# CAN_PHY.net
KiCad netlist of a schematic drawn in Altium Designer
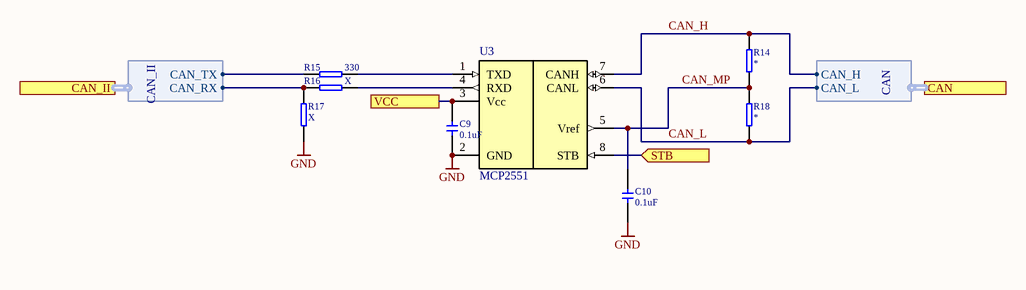
[diagram p0: CAN_PHY.SchDoc]

(export (version "E")
  (design (tool "Eeschema 10.0.6"))
  (components
    (comp (ref "C9")
      (value "0.1uF")
      (footprint "CERCAP 0603")
      (description "Capacitor")
      (fields (field (name "Comment") "CERCAP 0603 0.1uF * X7R"))
      (libsource (lib "!main") (part "!Capacitor"))
    )
    (comp (ref "C10")
      (value "0.1uF")
      (footprint "CERCAP 0603")
      (description "Capacitor")
      (fields (field (name "Comment") "CERCAP 0603 0.1uF * X7R"))
      (libsource (lib "!main") (part "!Capacitor"))
    )
    (comp (ref "R14")
      (value "RES 0603 *")
      (footprint "RES 0603")
      (description "Resistor")
      (fields (field (name "ALTIUM_VALUE") "*"))
      (libsource (lib "!main") (part "!Resistor"))
    )
    (comp (ref "R15")
      (value "330")
      (footprint "RES 0603")
      (description "Resistor")
      (fields (field (name "Comment") "RES 0603 330"))
      (libsource (lib "!main") (part "!Resistor"))
    )
    (comp (ref "R16")
      (value "X")
      (footprint "RES 0603")
      (description "Resistor")
      (fields (field (name "Comment") "RES 0603 X"))
      (libsource (lib "!main") (part "!Resistor"))
    )
    (comp (ref "R17")
      (value "X")
      (footprint "RES 0603")
      (description "Resistor")
      (fields (field (name "Comment") "RES 0603 X"))
      (libsource (lib "!main") (part "!Resistor"))
    )
    (comp (ref "R18")
      (value "RES 0603 *")
      (footprint "RES 0603")
      (description "Resistor")
      (fields (field (name "ALTIUM_VALUE") "*"))
      (libsource (lib "!main") (part "!Resistor"))
    )
    (comp (ref "U3")
      (value "MCP2551")
      (footprint "SO-8")
      (description "CAN PHY")
      (libsource (lib "interfaces") (part "CAN_PHY"))
    )
  )
  (nets
    (net (code "3") (name "/CAN_H") (class "Default")
      (node (ref "R14") (pin "2") (pinfunction "12_2") (pintype "passive"))
      (node (ref "U3") (pin "7") (pinfunction "CANH_7") (pintype "bidirectional"))
    )
    (net (code "4") (name "/CAN_L") (class "Default")
      (node (ref "R18") (pin "1") (pinfunction "11_1") (pintype "passive"))
      (node (ref "U3") (pin "6") (pinfunction "CANL_6") (pintype "bidirectional"))
    )
    (net (code "5") (name "/CAN_MP") (class "Default")
      (node (ref "C10") (pin "2") (pintype "passive"))
      (node (ref "R14") (pin "1") (pinfunction "11_1") (pintype "passive"))
      (node (ref "R18") (pin "2") (pinfunction "12_2") (pintype "passive"))
      (node (ref "U3") (pin "5") (pinfunction "Vref_5") (pintype "output"))
    )
    (net (code "6") (name "/CAN_RX") (class "Default")
      (node (ref "R16") (pin "1") (pinfunction "11_1") (pintype "passive"))
      (node (ref "R17") (pin "2") (pinfunction "12_2") (pintype "passive"))
    )
    (net (code "7") (name "/CAN_TX") (class "Default")
      (node (ref "R15") (pin "1") (pinfunction "11_1") (pintype "passive"))
    )
    (net (code "8") (name "/STB") (class "Default")
      (node (ref "U3") (pin "8") (pinfunction "STB_8") (pintype "input"))
    )
    (net (code "9") (name "/VCC") (class "Default")
      (node (ref "C9") (pin "2") (pintype "passive"))
      (node (ref "U3") (pin "3") (pinfunction "Vcc_3") (pintype "power_in"))
    )
    (net (code "12") (name "GND") (class "Default")
      (node (ref "C10") (pin "1") (pintype "passive"))
      (node (ref "C9") (pin "1") (pintype "passive"))
      (node (ref "R17") (pin "1") (pinfunction "11_1") (pintype "passive"))
      (node (ref "U3") (pin "2") (pinfunction "GND_2") (pintype "power_in"))
    )
    (net (code "13") (name "Net-(R15-12)") (class "Default")
      (node (ref "R15") (pin "2") (pinfunction "12_2") (pintype "passive"))
      (node (ref "U3") (pin "1") (pinfunction "TXD_1") (pintype "input"))
    )
    (net (code "14") (name "Net-(R16-12)") (class "Default")
      (node (ref "R16") (pin "2") (pinfunction "12_2") (pintype "passive"))
      (node (ref "U3") (pin "4") (pinfunction "RXD_4") (pintype "output"))
    )
  )
)
